# SatUplink-v12.net
KiCad netlist of a schematic drawn in EAGLE
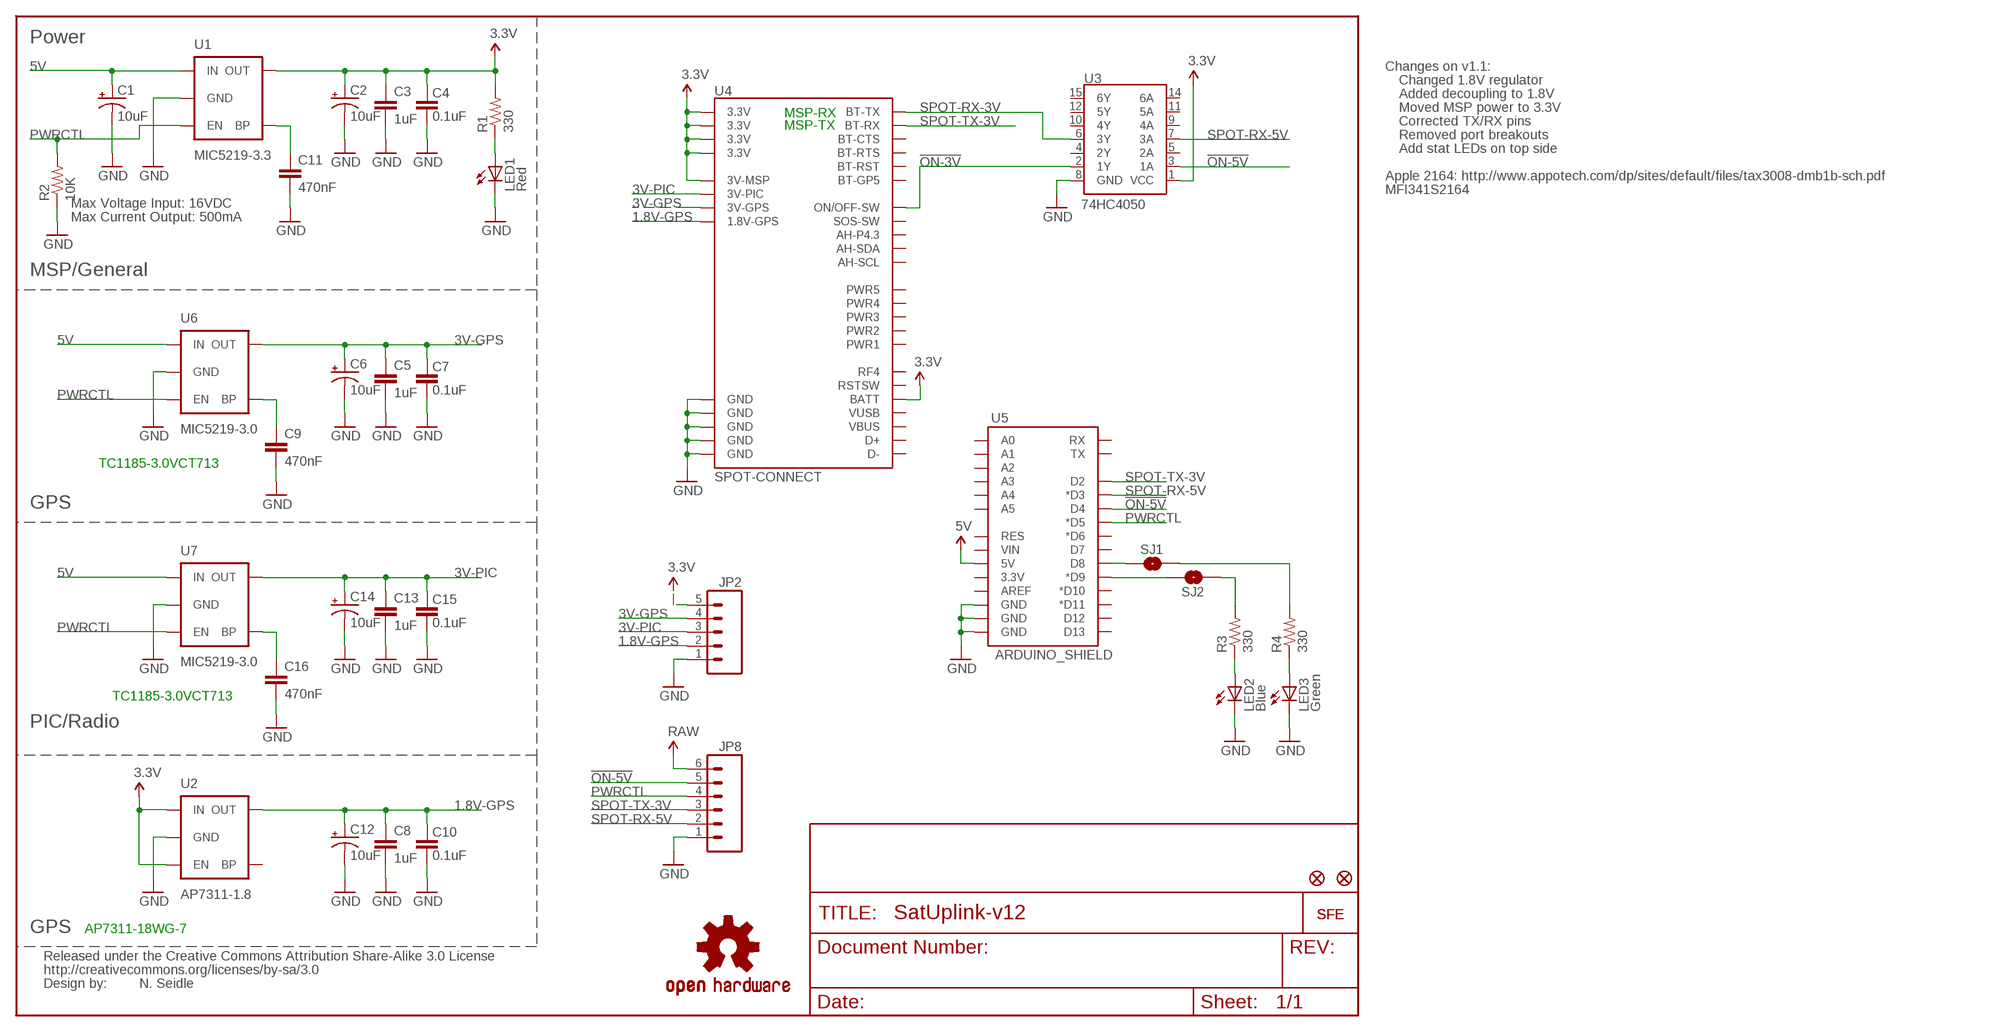
[diagram p0: schematic, sheet 1]

(export (version "E")
  (design (tool "Eeschema 10.0.6"))
  (components
    (comp (ref "C1")
      (value "10uF")
      (footprint "eagle-import:EIA3216")
      (libsource (lib "eagle-import") (part "CAP_POL1206"))
    )
    (comp (ref "C2")
      (value "10uF")
      (footprint "eagle-import:EIA3216")
      (libsource (lib "eagle-import") (part "CAP_POL1206"))
    )
    (comp (ref "C3")
      (value "1uF")
      (footprint "eagle-import:0402-CAP")
      (libsource (lib "eagle-import") (part "CAP0402-CAP"))
    )
    (comp (ref "C4")
      (value "0.1uF")
      (footprint "eagle-import:0402-CAP")
      (libsource (lib "eagle-import") (part "CAP0402-CAP"))
    )
    (comp (ref "C5")
      (value "1uF")
      (footprint "eagle-import:0402-CAP")
      (libsource (lib "eagle-import") (part "CAP0402-CAP"))
    )
    (comp (ref "C6")
      (value "10uF")
      (footprint "eagle-import:EIA3216")
      (libsource (lib "eagle-import") (part "CAP_POL1206"))
    )
    (comp (ref "C7")
      (value "0.1uF")
      (footprint "eagle-import:0402-CAP")
      (libsource (lib "eagle-import") (part "CAP0402-CAP"))
    )
    (comp (ref "C8")
      (value "1uF")
      (footprint "eagle-import:0402-CAP")
      (libsource (lib "eagle-import") (part "CAP0402-CAP"))
    )
    (comp (ref "C9")
      (value "470nF")
      (footprint "eagle-import:0402-CAP")
      (libsource (lib "eagle-import") (part "CAP0402-CAP"))
    )
    (comp (ref "C10")
      (value "0.1uF")
      (footprint "eagle-import:0402-CAP")
      (libsource (lib "eagle-import") (part "CAP0402-CAP"))
    )
    (comp (ref "C11")
      (value "470nF")
      (footprint "eagle-import:0402-CAP")
      (libsource (lib "eagle-import") (part "CAP0402-CAP"))
    )
    (comp (ref "C12")
      (value "10uF")
      (footprint "eagle-import:EIA3216")
      (libsource (lib "eagle-import") (part "CAP_POL1206"))
    )
    (comp (ref "C13")
      (value "1uF")
      (footprint "eagle-import:0402-CAP")
      (libsource (lib "eagle-import") (part "CAP0402-CAP"))
    )
    (comp (ref "C14")
      (value "10uF")
      (footprint "eagle-import:EIA3216")
      (libsource (lib "eagle-import") (part "CAP_POL1206"))
    )
    (comp (ref "C15")
      (value "0.1uF")
      (footprint "eagle-import:0402-CAP")
      (libsource (lib "eagle-import") (part "CAP0402-CAP"))
    )
    (comp (ref "C16")
      (value "470nF")
      (footprint "eagle-import:0402-CAP")
      (libsource (lib "eagle-import") (part "CAP0402-CAP"))
    )
    (comp (ref "JP2")
      (value "M05PTH")
      (footprint "eagle-import:1X05")
      (libsource (lib "eagle-import") (part "M05PTH"))
    )
    (comp (ref "JP8")
      (value "M06SIP")
      (footprint "eagle-import:1X06")
      (libsource (lib "eagle-import") (part "M06SIP"))
    )
    (comp (ref "JP10")
      (value "FIDUCIALUFIDUCIAL")
      (footprint "eagle-import:MICRO-FIDUCIAL")
      (libsource (lib "eagle-import") (part "FIDUCIALUFIDUCIAL"))
    )
    (comp (ref "JP11")
      (value "FIDUCIALUFIDUCIAL")
      (footprint "eagle-import:MICRO-FIDUCIAL")
      (libsource (lib "eagle-import") (part "FIDUCIALUFIDUCIAL"))
    )
    (comp (ref "LED1")
      (value "Red")
      (footprint "eagle-import:LED-0603")
      (libsource (lib "eagle-import") (part "LED0603"))
    )
    (comp (ref "LED2")
      (value "Blue")
      (footprint "eagle-import:LED-0603")
      (libsource (lib "eagle-import") (part "LED0603"))
    )
    (comp (ref "LED3")
      (value "Green")
      (footprint "eagle-import:LED-0603")
      (libsource (lib "eagle-import") (part "LED0603"))
    )
    (comp (ref "R1")
      (value "330")
      (footprint "eagle-import:0402-RES")
      (libsource (lib "eagle-import") (part "RESISTOR0402-RES"))
    )
    (comp (ref "R2")
      (value "10K")
      (footprint "eagle-import:0402-RES")
      (libsource (lib "eagle-import") (part "RESISTOR0402-RES"))
    )
    (comp (ref "R3")
      (value "330")
      (footprint "eagle-import:0402-RES")
      (libsource (lib "eagle-import") (part "RESISTOR0402-RES"))
    )
    (comp (ref "R4")
      (value "330")
      (footprint "eagle-import:0402-RES")
      (libsource (lib "eagle-import") (part "RESISTOR0402-RES"))
    )
    (comp (ref "SJ1")
      (value "SOLDERJUMPERTRACE")
      (footprint "eagle-import:SJ_2S-TRACE")
      (libsource (lib "eagle-import") (part "SOLDERJUMPERTRACE"))
    )
    (comp (ref "SJ2")
      (value "SOLDERJUMPERTRACE")
      (footprint "eagle-import:SJ_2S-TRACE")
      (libsource (lib "eagle-import") (part "SOLDERJUMPERTRACE"))
    )
    (comp (ref "U$1")
      (value "LOGO-SFESK")
      (footprint "eagle-import:SFE-LOGO-FLAME")
      (libsource (lib "eagle-import") (part "LOGO-SFESK"))
    )
    (comp (ref "U$2")
      (value "CREATIVE_COMMONS")
      (footprint "eagle-import:CREATIVE_COMMONS")
      (libsource (lib "eagle-import") (part "CREATIVE_COMMONS"))
    )
    (comp (ref "U$3")
      (value "OSHW-LOGOS")
      (footprint "eagle-import:OSHW-LOGO-S")
      (libsource (lib "eagle-import") (part "OSHW-LOGOS"))
    )
    (comp (ref "U$11")
      (value "LOGO-SFENEW")
      (footprint "eagle-import:SFE-NEW-WEBLOGO")
      (libsource (lib "eagle-import") (part "LOGO-SFENEW"))
    )
    (comp (ref "U1")
      (value "MIC5219-3.3")
      (footprint "eagle-import:SOT23-5")
      (libsource (lib "eagle-import") (part "V_REG_LDOSMD"))
    )
    (comp (ref "U2")
      (value "AP7311-1.8")
      (footprint "eagle-import:SOT23-5")
      (libsource (lib "eagle-import") (part "V_REG_LDOSMD"))
    )
    (comp (ref "U3")
      (value "74HC4050")
      (footprint "eagle-import:SO016")
      (libsource (lib "eagle-import") (part "HEX_CONVERTER"))
    )
    (comp (ref "U4")
      (value "SPOT-CONNECT")
      (footprint "eagle-import:SPOT-CONNECT")
      (libsource (lib "eagle-import") (part "SPOT-CONNECTSMD"))
    )
    (comp (ref "U5")
      (value "ARDUINO_SHIELD")
      (footprint "eagle-import:DUEMILANOVE_VIAS")
      (libsource (lib "eagle-import") (part "ARDUINO_SHIELDNO_SILK"))
    )
    (comp (ref "U6")
      (value "MIC5219-3.0")
      (footprint "eagle-import:SOT23-5")
      (libsource (lib "eagle-import") (part "V_REG_LDOSMD"))
    )
    (comp (ref "U7")
      (value "MIC5219-3.0")
      (footprint "eagle-import:SOT23-5")
      (libsource (lib "eagle-import") (part "V_REG_LDOSMD"))
    )
  )
  (nets
    (net (code "1") (name "/1.8V-GPS") (class "Default")
      (node (ref "C10") (pin "2") (pinfunction "2_2") (pintype "passive"))
      (node (ref "C12") (pin "A") (pinfunction "+_A") (pintype "passive"))
      (node (ref "C8") (pin "1") (pinfunction "1_1") (pintype "passive"))
      (node (ref "JP2") (pin "2") (pinfunction "2_2") (pintype "passive"))
      (node (ref "U2") (pin "5") (pinfunction "OUT_5") (pintype "passive"))
      (node (ref "U4") (pin "1.8V-GPS") (pinfunction "1.8V-GPS_1.8V-GPS") (pintype "bidirectional"))
    )
    (net (code "2") (name "/3V-GPS") (class "Default")
      (node (ref "C5") (pin "1") (pinfunction "1_1") (pintype "passive"))
      (node (ref "C6") (pin "A") (pinfunction "+_A") (pintype "passive"))
      (node (ref "C7") (pin "2") (pinfunction "2_2") (pintype "passive"))
      (node (ref "JP2") (pin "4") (pinfunction "4_4") (pintype "passive"))
      (node (ref "U4") (pin "3V-GPS") (pinfunction "3V-GPS_3V-GPS") (pintype "bidirectional"))
      (node (ref "U6") (pin "5") (pinfunction "OUT_5") (pintype "passive"))
    )
    (net (code "3") (name "/3V-PIC") (class "Default")
      (node (ref "C13") (pin "1") (pinfunction "1_1") (pintype "passive"))
      (node (ref "C14") (pin "A") (pinfunction "+_A") (pintype "passive"))
      (node (ref "C15") (pin "2") (pinfunction "2_2") (pintype "passive"))
      (node (ref "JP2") (pin "3") (pinfunction "3_3") (pintype "passive"))
      (node (ref "U4") (pin "3VPIC") (pinfunction "3V-PIC_3VPIC") (pintype "bidirectional"))
      (node (ref "U7") (pin "5") (pinfunction "OUT_5") (pintype "passive"))
    )
    (net (code "4") (name "/PWRCTL") (class "Default")
      (node (ref "JP8") (pin "4") (pinfunction "4_4") (pintype "passive"))
      (node (ref "R2") (pin "2") (pinfunction "2_2") (pintype "passive"))
      (node (ref "U1") (pin "3") (pinfunction "EN_3") (pintype "input"))
      (node (ref "U5") (pin "D5") (pinfunction "*D5_D5") (pintype "bidirectional"))
      (node (ref "U6") (pin "3") (pinfunction "EN_3") (pintype "input"))
      (node (ref "U7") (pin "3") (pinfunction "EN_3") (pintype "input"))
    )
    (net (code "5") (name "/SPOT-RX-3V") (class "Default")
      (node (ref "U3") (pin "6") (pinfunction "3Y_6") (pintype "bidirectional"))
      (node (ref "U4") (pin "BT-TX") (pinfunction "BT-TX_BT-TX") (pintype "bidirectional"))
    )
    (net (code "6") (name "/SPOT-RX-5V") (class "Default")
      (node (ref "JP8") (pin "2") (pinfunction "2_2") (pintype "passive"))
      (node (ref "U3") (pin "7") (pinfunction "3A_7") (pintype "bidirectional"))
      (node (ref "U5") (pin "D3") (pinfunction "*D3_D3") (pintype "bidirectional"))
    )
    (net (code "7") (name "/SPOT-TX-3V") (class "Default")
      (node (ref "JP8") (pin "3") (pinfunction "3_3") (pintype "passive"))
      (node (ref "U4") (pin "BT-RX") (pinfunction "BT-RX_BT-RX") (pintype "bidirectional"))
      (node (ref "U5") (pin "D2") (pinfunction "D2_D2") (pintype "bidirectional"))
    )
    (net (code "8") (name "/~{ON-3V}") (class "Default")
      (node (ref "U3") (pin "2") (pinfunction "1Y_2") (pintype "bidirectional"))
      (node (ref "U4") (pin "ON/OFF") (pinfunction "ON/OFF-SW_ON/OFF") (pintype "bidirectional"))
    )
    (net (code "9") (name "/~{ON-5V}") (class "Default")
      (node (ref "JP8") (pin "5") (pinfunction "5_5") (pintype "passive"))
      (node (ref "U3") (pin "3") (pinfunction "1A_3") (pintype "bidirectional"))
      (node (ref "U5") (pin "D4") (pinfunction "D4_D4") (pintype "bidirectional"))
    )
    (net (code "10") (name "3.3V") (class "Default")
      (node (ref "C2") (pin "A") (pinfunction "+_A") (pintype "passive"))
      (node (ref "C3") (pin "1") (pinfunction "1_1") (pintype "passive"))
      (node (ref "C4") (pin "2") (pinfunction "2_2") (pintype "passive"))
      (node (ref "JP2") (pin "5") (pinfunction "5_5") (pintype "passive"))
      (node (ref "R1") (pin "2") (pinfunction "2_2") (pintype "passive"))
      (node (ref "U1") (pin "5") (pinfunction "OUT_5") (pintype "passive"))
      (node (ref "U2") (pin "1") (pinfunction "IN_1") (pintype "input"))
      (node (ref "U2") (pin "3") (pinfunction "EN_3") (pintype "input"))
      (node (ref "U3") (pin "1") (pinfunction "VCC_1") (pintype "bidirectional"))
      (node (ref "U4") (pin "3.3V@1") (pinfunction "3.3V_3.3V@1") (pintype "bidirectional"))
      (node (ref "U4") (pin "3.3V@2") (pinfunction "3.3V_3.3V@2") (pintype "bidirectional"))
      (node (ref "U4") (pin "3.3V@3") (pinfunction "3.3V_3.3V@3") (pintype "bidirectional"))
      (node (ref "U4") (pin "3.3V@4") (pinfunction "3.3V_3.3V@4") (pintype "bidirectional"))
      (node (ref "U4") (pin "3VMSP") (pinfunction "3V-MSP_3VMSP") (pintype "bidirectional"))
      (node (ref "U4") (pin "BATT") (pinfunction "BATT_BATT") (pintype "bidirectional"))
    )
    (net (code "11") (name "5V") (class "Default")
      (node (ref "C1") (pin "A") (pinfunction "+_A") (pintype "passive"))
      (node (ref "JP8") (pin "6") (pinfunction "6_6") (pintype "passive"))
      (node (ref "U1") (pin "1") (pinfunction "IN_1") (pintype "input"))
      (node (ref "U5") (pin "5V") (pinfunction "5V_5V") (pintype "bidirectional"))
      (node (ref "U6") (pin "1") (pinfunction "IN_1") (pintype "input"))
      (node (ref "U7") (pin "1") (pinfunction "IN_1") (pintype "input"))
    )
    (net (code "12") (name "GND") (class "Default")
      (node (ref "C1") (pin "C") (pinfunction "-_C") (pintype "passive"))
      (node (ref "C10") (pin "1") (pinfunction "1_1") (pintype "passive"))
      (node (ref "C11") (pin "2") (pinfunction "2_2") (pintype "passive"))
      (node (ref "C12") (pin "C") (pinfunction "-_C") (pintype "passive"))
      (node (ref "C13") (pin "2") (pinfunction "2_2") (pintype "passive"))
      (node (ref "C14") (pin "C") (pinfunction "-_C") (pintype "passive"))
      (node (ref "C15") (pin "1") (pinfunction "1_1") (pintype "passive"))
      (node (ref "C16") (pin "2") (pinfunction "2_2") (pintype "passive"))
      (node (ref "C2") (pin "C") (pinfunction "-_C") (pintype "passive"))
      (node (ref "C3") (pin "2") (pinfunction "2_2") (pintype "passive"))
      (node (ref "C4") (pin "1") (pinfunction "1_1") (pintype "passive"))
      (node (ref "C5") (pin "2") (pinfunction "2_2") (pintype "passive"))
      (node (ref "C6") (pin "C") (pinfunction "-_C") (pintype "passive"))
      (node (ref "C7") (pin "1") (pinfunction "1_1") (pintype "passive"))
      (node (ref "C8") (pin "2") (pinfunction "2_2") (pintype "passive"))
      (node (ref "C9") (pin "2") (pinfunction "2_2") (pintype "passive"))
      (node (ref "JP2") (pin "1") (pinfunction "1_1") (pintype "passive"))
      (node (ref "JP8") (pin "1") (pinfunction "1_1") (pintype "passive"))
      (node (ref "LED1") (pin "C") (pinfunction "C_C") (pintype "passive"))
      (node (ref "LED2") (pin "C") (pinfunction "C_C") (pintype "passive"))
      (node (ref "LED3") (pin "C") (pinfunction "C_C") (pintype "passive"))
      (node (ref "R2") (pin "1") (pinfunction "1_1") (pintype "passive"))
      (node (ref "U1") (pin "2") (pinfunction "GND_2") (pintype "input"))
      (node (ref "U2") (pin "2") (pinfunction "GND_2") (pintype "input"))
      (node (ref "U3") (pin "8") (pinfunction "GND_8") (pintype "bidirectional"))
      (node (ref "U4") (pin "GND@1") (pinfunction "GND_GND@1") (pintype "bidirectional"))
      (node (ref "U4") (pin "GND@2") (pinfunction "GND_GND@2") (pintype "bidirectional"))
      (node (ref "U4") (pin "GND@3") (pinfunction "GND_GND@3") (pintype "bidirectional"))
      (node (ref "U4") (pin "GND@4") (pinfunction "GND_GND@4") (pintype "bidirectional"))
      (node (ref "U4") (pin "GND@5") (pinfunction "GND_GND@5") (pintype "bidirectional"))
      (node (ref "U5") (pin "GND@0") (pinfunction "GND_GND@0") (pintype "bidirectional"))
      (node (ref "U5") (pin "GND@1") (pinfunction "GND_GND@1") (pintype "bidirectional"))
      (node (ref "U5") (pin "GND@2") (pinfunction "GND_GND@2") (pintype "bidirectional"))
      (node (ref "U6") (pin "2") (pinfunction "GND_2") (pintype "input"))
      (node (ref "U7") (pin "2") (pinfunction "GND_2") (pintype "input"))
    )
    (net (code "13") (name "Net-(LED1-PadA)") (class "Default")
      (node (ref "LED1") (pin "A") (pinfunction "A_A") (pintype "passive"))
      (node (ref "R1") (pin "1") (pinfunction "1_1") (pintype "passive"))
    )
    (net (code "14") (name "Net-(LED2-PadA)") (class "Default")
      (node (ref "LED2") (pin "A") (pinfunction "A_A") (pintype "passive"))
      (node (ref "R3") (pin "1") (pinfunction "1_1") (pintype "passive"))
    )
    (net (code "15") (name "Net-(LED3-PadA)") (class "Default")
      (node (ref "LED3") (pin "A") (pinfunction "A_A") (pintype "passive"))
      (node (ref "R4") (pin "1") (pinfunction "1_1") (pintype "passive"))
    )
    (net (code "16") (name "Net-(R3-Pad2)") (class "Default")
      (node (ref "R3") (pin "2") (pinfunction "2_2") (pintype "passive"))
      (node (ref "SJ2") (pin "2") (pinfunction "2_2") (pintype "passive"))
    )
    (net (code "17") (name "Net-(R4-Pad2)") (class "Default")
      (node (ref "R4") (pin "2") (pinfunction "2_2") (pintype "passive"))
      (node (ref "SJ1") (pin "2") (pinfunction "2_2") (pintype "passive"))
    )
    (net (code "18") (name "Net-(SJ1-Pad1)") (class "Default")
      (node (ref "SJ1") (pin "1") (pinfunction "1_1") (pintype "passive"))
      (node (ref "U5") (pin "D8") (pinfunction "D8_D8") (pintype "bidirectional"))
    )
    (net (code "19") (name "Net-(U1-BP)") (class "Default")
      (node (ref "C11") (pin "1") (pinfunction "1_1") (pintype "passive"))
      (node (ref "U1") (pin "4") (pinfunction "BP_4") (pintype "input"))
    )
    (net (code "20") (name "Net-(U5-*D9)") (class "Default")
      (node (ref "SJ2") (pin "1") (pinfunction "1_1") (pintype "passive"))
      (node (ref "U5") (pin "D9") (pinfunction "*D9_D9") (pintype "bidirectional"))
    )
    (net (code "21") (name "Net-(U6-BP)") (class "Default")
      (node (ref "C9") (pin "1") (pinfunction "1_1") (pintype "passive"))
      (node (ref "U6") (pin "4") (pinfunction "BP_4") (pintype "input"))
    )
    (net (code "22") (name "Net-(U7-BP)") (class "Default")
      (node (ref "C16") (pin "1") (pinfunction "1_1") (pintype "passive"))
      (node (ref "U7") (pin "4") (pinfunction "BP_4") (pintype "input"))
    )
    (net (code "23") (name "unconnected-(U2-BP-Pad4)") (class "Default")
      (node (ref "U2") (pin "4") (pinfunction "BP_4") (pintype "input"))
    )
    (net (code "24") (name "unconnected-(U3-2A-Pad5)") (class "Default")
      (node (ref "U3") (pin "5") (pinfunction "2A_5") (pintype "bidirectional"))
    )
    (net (code "25") (name "unconnected-(U3-2Y-Pad4)") (class "Default")
      (node (ref "U3") (pin "4") (pinfunction "2Y_4") (pintype "bidirectional"))
    )
    (net (code "26") (name "unconnected-(U3-4A-Pad9)") (class "Default")
      (node (ref "U3") (pin "9") (pinfunction "4A_9") (pintype "bidirectional"))
    )
    (net (code "27") (name "unconnected-(U3-4Y-Pad10)") (class "Default")
      (node (ref "U3") (pin "10") (pinfunction "4Y_10") (pintype "bidirectional"))
    )
    (net (code "28") (name "unconnected-(U3-5A-Pad11)") (class "Default")
      (node (ref "U3") (pin "11") (pinfunction "5A_11") (pintype "bidirectional"))
    )
    (net (code "29") (name "unconnected-(U3-5Y-Pad12)") (class "Default")
      (node (ref "U3") (pin "12") (pinfunction "5Y_12") (pintype "bidirectional"))
    )
    (net (code "30") (name "unconnected-(U3-6A-Pad14)") (class "Default")
      (node (ref "U3") (pin "14") (pinfunction "6A_14") (pintype "bidirectional"))
    )
    (net (code "31") (name "unconnected-(U3-6Y-Pad15)") (class "Default")
      (node (ref "U3") (pin "15") (pinfunction "6Y_15") (pintype "bidirectional"))
    )
    (net (code "32") (name "unconnected-(U4-AH-P4.3-PadAH{slash}P4.3)") (class "Default")
      (node (ref "U4") (pin "AH/P4.3") (pinfunction "AH-P4.3_AH/P4.3") (pintype "bidirectional"))
    )
    (net (code "33") (name "unconnected-(U4-AH-SDA-PadAH{slash}SDA)") (class "Default")
      (node (ref "U4") (pin "AH/SDA") (pinfunction "AH-SDA_AH/SDA") (pintype "bidirectional"))
    )
    (net (code "34") (name "unconnected-(U4-PWR1-PadPWRCTL1)") (class "Default")
      (node (ref "U4") (pin "PWRCTL1") (pinfunction "PWR1_PWRCTL1") (pintype "bidirectional"))
    )
    (net (code "35") (name "unconnected-(U4-PWR2-PadPWRCTL2)") (class "Default")
      (node (ref "U4") (pin "PWRCTL2") (pinfunction "PWR2_PWRCTL2") (pintype "bidirectional"))
    )
    (net (code "36") (name "unconnected-(U4-PWR3-PadPWRCTL3)") (class "Default")
      (node (ref "U4") (pin "PWRCTL3") (pinfunction "PWR3_PWRCTL3") (pintype "bidirectional"))
    )
    (net (code "37") (name "unconnected-(U4-PWR4-PadPWRCTL4)") (class "Default")
      (node (ref "U4") (pin "PWRCTL4") (pinfunction "PWR4_PWRCTL4") (pintype "bidirectional"))
    )
    (net (code "38") (name "unconnected-(U4-PWR5-PadPWRCTL5)") (class "Default")
      (node (ref "U4") (pin "PWRCTL5") (pinfunction "PWR5_PWRCTL5") (pintype "bidirectional"))
    )
    (net (code "39") (name "unconnected-(U4-PadAH-SCL)") (class "Default")
      (node (ref "U4") (pin "AH-SCL") (pinfunction "AH-SCL_AH-SCL") (pintype "bidirectional"))
    )
    (net (code "40") (name "unconnected-(U4-PadBT-CTS)") (class "Default")
      (node (ref "U4") (pin "BT-CTS") (pinfunction "BT-CTS_BT-CTS") (pintype "bidirectional"))
    )
    (net (code "41") (name "unconnected-(U4-PadBT-GP5)") (class "Default")
      (node (ref "U4") (pin "BT-GP5") (pinfunction "BT-GP5_BT-GP5") (pintype "bidirectional"))
    )
    (net (code "42") (name "unconnected-(U4-PadBT-RST)") (class "Default")
      (node (ref "U4") (pin "BT-RST") (pinfunction "BT-RST_BT-RST") (pintype "bidirectional"))
    )
    (net (code "43") (name "unconnected-(U4-PadBT-RTS)") (class "Default")
      (node (ref "U4") (pin "BT-RTS") (pinfunction "BT-RTS_BT-RTS") (pintype "bidirectional"))
    )
    (net (code "44") (name "unconnected-(U4-PadD+)") (class "Default")
      (node (ref "U4") (pin "D+") (pinfunction "D+_D+") (pintype "bidirectional"))
    )
    (net (code "45") (name "unconnected-(U4-PadD-)") (class "Default")
      (node (ref "U4") (pin "D-") (pinfunction "D-_D-") (pintype "bidirectional"))
    )
    (net (code "46") (name "unconnected-(U4-PadRF4)") (class "Default")
      (node (ref "U4") (pin "RF4") (pinfunction "RF4_RF4") (pintype "bidirectional"))
    )
    (net (code "47") (name "unconnected-(U4-PadRSTSW)") (class "Default")
      (node (ref "U4") (pin "RSTSW") (pinfunction "RSTSW_RSTSW") (pintype "bidirectional"))
    )
    (net (code "48") (name "unconnected-(U4-PadVBUS)") (class "Default")
      (node (ref "U4") (pin "VBUS") (pinfunction "VBUS_VBUS") (pintype "bidirectional"))
    )
    (net (code "49") (name "unconnected-(U4-PadVUSB)") (class "Default")
      (node (ref "U4") (pin "VUSB") (pinfunction "VUSB_VUSB") (pintype "bidirectional"))
    )
    (net (code "50") (name "unconnected-(U4-SOS-SW-PadSOS)") (class "Default")
      (node (ref "U4") (pin "SOS") (pinfunction "SOS-SW_SOS") (pintype "bidirectional"))
    )
    (net (code "51") (name "unconnected-(U5-*D6-PadD6)") (class "Default")
      (node (ref "U5") (pin "D6") (pinfunction "*D6_D6") (pintype "bidirectional"))
    )
    (net (code "52") (name "unconnected-(U5-*D10-PadD10)") (class "Default")
      (node (ref "U5") (pin "D10") (pinfunction "*D10_D10") (pintype "bidirectional"))
    )
    (net (code "53") (name "unconnected-(U5-*D11-PadD11)") (class "Default")
      (node (ref "U5") (pin "D11") (pinfunction "*D11_D11") (pintype "bidirectional"))
    )
    (net (code "54") (name "unconnected-(U5-Pad3.3V)") (class "Default")
      (node (ref "U5") (pin "3.3V") (pinfunction "3.3V_3.3V") (pintype "bidirectional"))
    )
    (net (code "55") (name "unconnected-(U5-PadA0)") (class "Default")
      (node (ref "U5") (pin "A0") (pinfunction "A0_A0") (pintype "bidirectional"))
    )
    (net (code "56") (name "unconnected-(U5-PadA1)") (class "Default")
      (node (ref "U5") (pin "A1") (pinfunction "A1_A1") (pintype "bidirectional"))
    )
    (net (code "57") (name "unconnected-(U5-PadA2)") (class "Default")
      (node (ref "U5") (pin "A2") (pinfunction "A2_A2") (pintype "bidirectional"))
    )
    (net (code "58") (name "unconnected-(U5-PadA3)") (class "Default")
      (node (ref "U5") (pin "A3") (pinfunction "A3_A3") (pintype "bidirectional"))
    )
    (net (code "59") (name "unconnected-(U5-PadA4)") (class "Default")
      (node (ref "U5") (pin "A4") (pinfunction "A4_A4") (pintype "bidirectional"))
    )
    (net (code "60") (name "unconnected-(U5-PadA5)") (class "Default")
      (node (ref "U5") (pin "A5") (pinfunction "A5_A5") (pintype "bidirectional"))
    )
    (net (code "61") (name "unconnected-(U5-PadAREF)") (class "Default")
      (node (ref "U5") (pin "AREF") (pinfunction "AREF_AREF") (pintype "bidirectional"))
    )
    (net (code "62") (name "unconnected-(U5-PadD7)") (class "Default")
      (node (ref "U5") (pin "D7") (pinfunction "D7_D7") (pintype "bidirectional"))
    )
    (net (code "63") (name "unconnected-(U5-PadD12)") (class "Default")
      (node (ref "U5") (pin "D12") (pinfunction "D12_D12") (pintype "bidirectional"))
    )
    (net (code "64") (name "unconnected-(U5-PadD13)") (class "Default")
      (node (ref "U5") (pin "D13") (pinfunction "D13_D13") (pintype "bidirectional"))
    )
    (net (code "65") (name "unconnected-(U5-PadRES)") (class "Default")
      (node (ref "U5") (pin "RES") (pinfunction "RES_RES") (pintype "bidirectional"))
    )
    (net (code "66") (name "unconnected-(U5-PadRX)") (class "Default")
      (node (ref "U5") (pin "RX") (pinfunction "RX_RX") (pintype "bidirectional"))
    )
    (net (code "67") (name "unconnected-(U5-PadTX)") (class "Default")
      (node (ref "U5") (pin "TX") (pinfunction "TX_TX") (pintype "bidirectional"))
    )
    (net (code "68") (name "unconnected-(U5-PadVIN)") (class "Default")
      (node (ref "U5") (pin "VIN") (pinfunction "VIN_VIN") (pintype "bidirectional"))
    )
  )
)
